# MarsLander.net
KiCad netlist of a schematic drawn in EAGLE
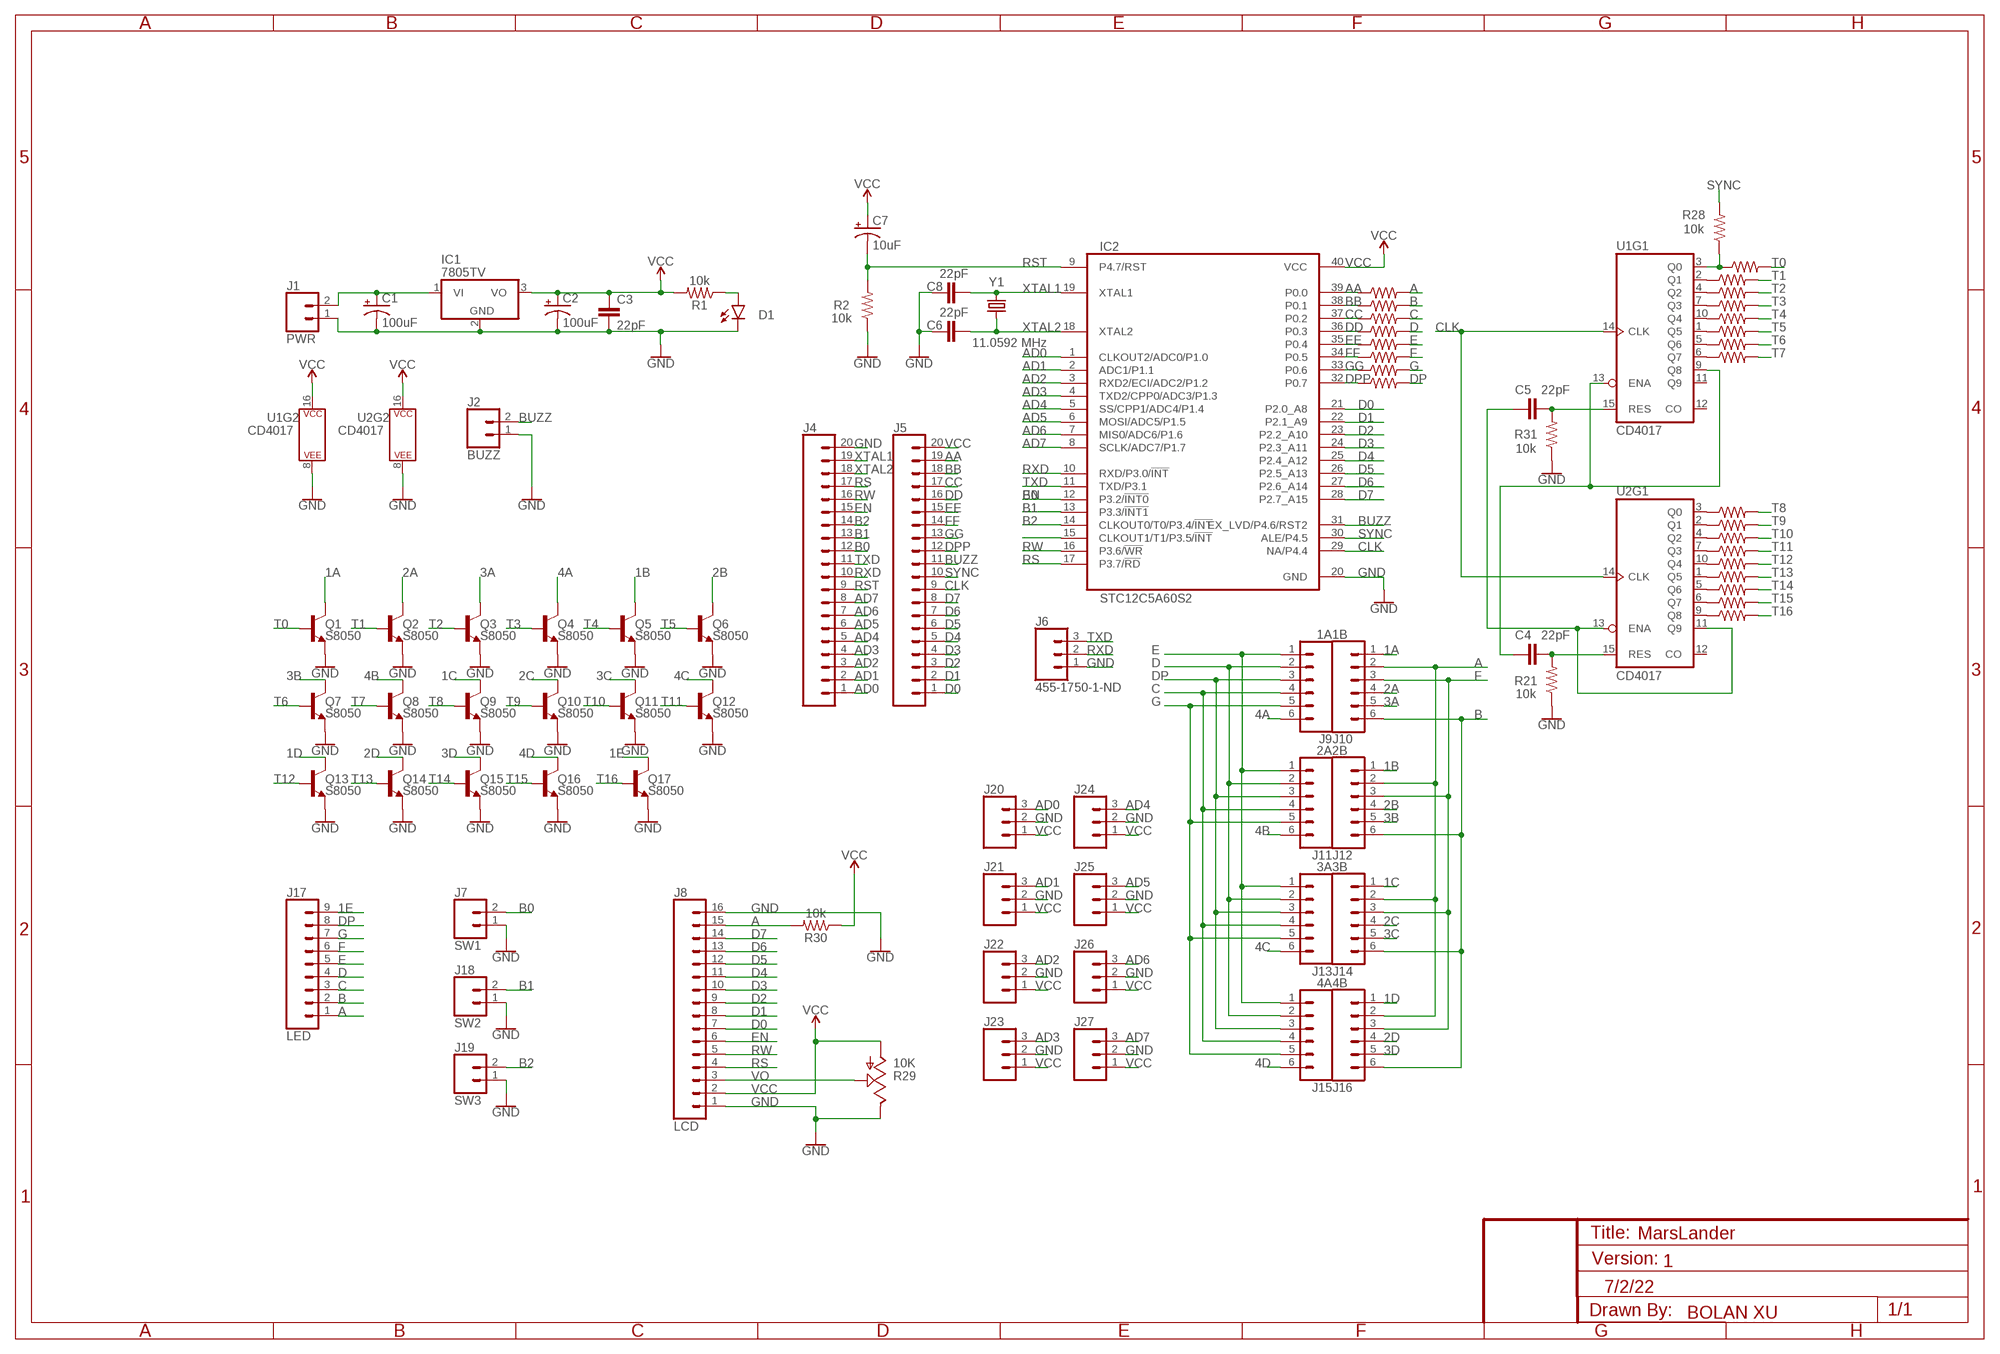
[diagram p0: schematic, sheet 1]

(export (version "E")
  (design (tool "Eeschema 10.0.6"))
  (components
    (comp (ref "C1")
      (value "100uF")
      (footprint "eagle-import:CPOL-RADIAL-2.5MM-6.5MM")
      (libsource (lib "eagle-import") (part "100UF-POLAR-RADIAL-2.5MM-25V-20%"))
    )
    (comp (ref "C2")
      (value "100uF")
      (footprint "eagle-import:CPOL-RADIAL-2.5MM-6.5MM")
      (libsource (lib "eagle-import") (part "100UF-POLAR-RADIAL-2.5MM-25V-20%"))
    )
    (comp (ref "C3")
      (value "22pF")
      (footprint "eagle-import:CAP-PTH-2.54")
      (libsource (lib "eagle-import") (part "22PF-PTH-2.54MM-200V-5%"))
    )
    (comp (ref "C4")
      (value "22pF")
      (footprint "eagle-import:CAP-PTH-2.54")
      (libsource (lib "eagle-import") (part "22PF-PTH-2.54MM-200V-5%"))
    )
    (comp (ref "C5")
      (value "22pF")
      (footprint "eagle-import:CAP-PTH-2.54")
      (libsource (lib "eagle-import") (part "22PF-PTH-2.54MM-200V-5%"))
    )
    (comp (ref "C6")
      (value "22pF")
      (footprint "eagle-import:CAP-PTH-2.54")
      (libsource (lib "eagle-import") (part "22PF-PTH-2.54MM-200V-5%"))
    )
    (comp (ref "C7")
      (value "10uF")
      (footprint "eagle-import:CPOL-RADIAL-2.5MM-5MM")
      (libsource (lib "eagle-import") (part "10UF-POLAR-RADIAL-2.5MM-25V-20%"))
    )
    (comp (ref "C8")
      (value "22pF")
      (footprint "eagle-import:CAP-PTH-2.54")
      (libsource (lib "eagle-import") (part "22PF-PTH-2.54MM-200V-5%"))
    )
    (comp (ref "D1")
      (value "3MM")
      (footprint "eagle-import:LED_3MM")
      (libsource (lib "eagle-import") (part "LED3MM"))
    )
    (comp (ref "IC1")
      (value "7805TV")
      (footprint "eagle-import:TO220V")
      (libsource (lib "eagle-import") (part "78TV05"))
    )
    (comp (ref "IC2")
      (value "STC12C5A60S2")
      (footprint "eagle-import:DIL40")
      (libsource (lib "eagle-import") (part "STC125A60S2P"))
    )
    (comp (ref "J1")
      (value "PWR")
      (footprint "eagle-import:1X02")
      (libsource (lib "eagle-import") (part "CONN_02"))
    )
    (comp (ref "J2")
      (value "BUZZ")
      (footprint "eagle-import:1X02")
      (libsource (lib "eagle-import") (part "CONN_02"))
    )
    (comp (ref "J4")
      (value "CONN_20")
      (footprint "eagle-import:1X20")
      (libsource (lib "eagle-import") (part "CONN_20"))
    )
    (comp (ref "J5")
      (value "CONN_20")
      (footprint "eagle-import:1X20")
      (libsource (lib "eagle-import") (part "CONN_20"))
    )
    (comp (ref "J6")
      (value "455-1750-1-ND")
      (footprint "eagle-import:1X03")
      (libsource (lib "eagle-import") (part "CONN_03"))
    )
    (comp (ref "J7")
      (value "SW1")
      (footprint "eagle-import:1X02")
      (libsource (lib "eagle-import") (part "CONN_02"))
    )
    (comp (ref "J8")
      (value "LCD")
      (footprint "eagle-import:1X16")
      (libsource (lib "eagle-import") (part "CONN_16"))
    )
    (comp (ref "J9")
      (value "1A")
      (footprint "eagle-import:1X06")
      (libsource (lib "eagle-import") (part "CONN_06SILK_FEMALE_PTH"))
    )
    (comp (ref "J10")
      (value "1B")
      (footprint "eagle-import:1X06")
      (libsource (lib "eagle-import") (part "CONN_06SILK_FEMALE_PTH"))
    )
    (comp (ref "J11")
      (value "2A")
      (footprint "eagle-import:1X06")
      (libsource (lib "eagle-import") (part "CONN_06SILK_FEMALE_PTH"))
    )
    (comp (ref "J12")
      (value "2B")
      (footprint "eagle-import:1X06")
      (libsource (lib "eagle-import") (part "CONN_06SILK_FEMALE_PTH"))
    )
    (comp (ref "J13")
      (value "3A")
      (footprint "eagle-import:1X06")
      (libsource (lib "eagle-import") (part "CONN_06SILK_FEMALE_PTH"))
    )
    (comp (ref "J14")
      (value "3B")
      (footprint "eagle-import:1X06")
      (libsource (lib "eagle-import") (part "CONN_06SILK_FEMALE_PTH"))
    )
    (comp (ref "J15")
      (value "4A")
      (footprint "eagle-import:1X06")
      (libsource (lib "eagle-import") (part "CONN_06SILK_FEMALE_PTH"))
    )
    (comp (ref "J16")
      (value "4B")
      (footprint "eagle-import:1X06")
      (libsource (lib "eagle-import") (part "CONN_06SILK_FEMALE_PTH"))
    )
    (comp (ref "J17")
      (value "LED")
      (footprint "eagle-import:1X09")
      (libsource (lib "eagle-import") (part "CONN_09"))
    )
    (comp (ref "J18")
      (value "SW2")
      (footprint "eagle-import:1X02")
      (libsource (lib "eagle-import") (part "CONN_02"))
    )
    (comp (ref "J19")
      (value "SW3")
      (footprint "eagle-import:1X02")
      (libsource (lib "eagle-import") (part "CONN_02"))
    )
    (comp (ref "J20")
      (value "455-1750-1-ND")
      (footprint "eagle-import:1X03")
      (libsource (lib "eagle-import") (part "CONN_03"))
    )
    (comp (ref "J21")
      (value "455-1750-1-ND")
      (footprint "eagle-import:1X03")
      (libsource (lib "eagle-import") (part "CONN_03"))
    )
    (comp (ref "J22")
      (value "455-1750-1-ND")
      (footprint "eagle-import:1X03")
      (libsource (lib "eagle-import") (part "CONN_03"))
    )
    (comp (ref "J23")
      (value "455-1750-1-ND")
      (footprint "eagle-import:1X03")
      (libsource (lib "eagle-import") (part "CONN_03"))
    )
    (comp (ref "J24")
      (value "455-1750-1-ND")
      (footprint "eagle-import:1X03")
      (libsource (lib "eagle-import") (part "CONN_03"))
    )
    (comp (ref "J25")
      (value "455-1750-1-ND")
      (footprint "eagle-import:1X03")
      (libsource (lib "eagle-import") (part "CONN_03"))
    )
    (comp (ref "J26")
      (value "455-1750-1-ND")
      (footprint "eagle-import:1X03")
      (libsource (lib "eagle-import") (part "CONN_03"))
    )
    (comp (ref "J27")
      (value "455-1750-1-ND")
      (footprint "eagle-import:1X03")
      (libsource (lib "eagle-import") (part "CONN_03"))
    )
    (comp (ref "Q1")
      (value "S8050")
      (footprint "eagle-import:TO-92")
      (libsource (lib "eagle-import") (part "TRANS_NPN-2N3904"))
    )
    (comp (ref "Q2")
      (value "S8050")
      (footprint "eagle-import:TO-92")
      (libsource (lib "eagle-import") (part "TRANS_NPN-2N3904"))
    )
    (comp (ref "Q3")
      (value "S8050")
      (footprint "eagle-import:TO-92")
      (libsource (lib "eagle-import") (part "TRANS_NPN-2N3904"))
    )
    (comp (ref "Q4")
      (value "S8050")
      (footprint "eagle-import:TO-92")
      (libsource (lib "eagle-import") (part "TRANS_NPN-2N3904"))
    )
    (comp (ref "Q5")
      (value "S8050")
      (footprint "eagle-import:TO-92")
      (libsource (lib "eagle-import") (part "TRANS_NPN-2N3904"))
    )
    (comp (ref "Q6")
      (value "S8050")
      (footprint "eagle-import:TO-92")
      (libsource (lib "eagle-import") (part "TRANS_NPN-2N3904"))
    )
    (comp (ref "Q7")
      (value "S8050")
      (footprint "eagle-import:TO-92")
      (libsource (lib "eagle-import") (part "TRANS_NPN-2N3904"))
    )
    (comp (ref "Q8")
      (value "S8050")
      (footprint "eagle-import:TO-92")
      (libsource (lib "eagle-import") (part "TRANS_NPN-2N3904"))
    )
    (comp (ref "Q9")
      (value "S8050")
      (footprint "eagle-import:TO-92")
      (libsource (lib "eagle-import") (part "TRANS_NPN-2N3904"))
    )
    (comp (ref "Q10")
      (value "S8050")
      (footprint "eagle-import:TO-92")
      (libsource (lib "eagle-import") (part "TRANS_NPN-2N3904"))
    )
    (comp (ref "Q11")
      (value "S8050")
      (footprint "eagle-import:TO-92")
      (libsource (lib "eagle-import") (part "TRANS_NPN-2N3904"))
    )
    (comp (ref "Q12")
      (value "S8050")
      (footprint "eagle-import:TO-92")
      (libsource (lib "eagle-import") (part "TRANS_NPN-2N3904"))
    )
    (comp (ref "Q13")
      (value "S8050")
      (footprint "eagle-import:TO-92")
      (libsource (lib "eagle-import") (part "TRANS_NPN-2N3904"))
    )
    (comp (ref "Q14")
      (value "S8050")
      (footprint "eagle-import:TO-92")
      (libsource (lib "eagle-import") (part "TRANS_NPN-2N3904"))
    )
    (comp (ref "Q15")
      (value "S8050")
      (footprint "eagle-import:TO-92")
      (libsource (lib "eagle-import") (part "TRANS_NPN-2N3904"))
    )
    (comp (ref "Q16")
      (value "S8050")
      (footprint "eagle-import:TO-92")
      (libsource (lib "eagle-import") (part "TRANS_NPN-2N3904"))
    )
    (comp (ref "Q17")
      (value "S8050")
      (footprint "eagle-import:TO-92")
      (libsource (lib "eagle-import") (part "TRANS_NPN-2N3904"))
    )
    (comp (ref "R1")
      (value "10k")
      (footprint "eagle-import:AXIAL-0.3")
      (libsource (lib "eagle-import") (part "10KOHM-HORIZ-1/4W-1%"))
    )
    (comp (ref "R2")
      (value "10k")
      (footprint "eagle-import:AXIAL-0.3")
      (libsource (lib "eagle-import") (part "10KOHM-HORIZ-1/4W-1%"))
    )
    (comp (ref "R3")
      (value "10k")
      (footprint "eagle-import:AXIAL-0.3")
      (libsource (lib "eagle-import") (part "10KOHM-HORIZ-1/4W-1%"))
    )
    (comp (ref "R4")
      (value "10k")
      (footprint "eagle-import:AXIAL-0.3")
      (libsource (lib "eagle-import") (part "10KOHM-HORIZ-1/4W-1%"))
    )
    (comp (ref "R5")
      (value "10k")
      (footprint "eagle-import:AXIAL-0.3")
      (libsource (lib "eagle-import") (part "10KOHM-HORIZ-1/4W-1%"))
    )
    (comp (ref "R6")
      (value "10k")
      (footprint "eagle-import:AXIAL-0.3")
      (libsource (lib "eagle-import") (part "10KOHM-HORIZ-1/4W-1%"))
    )
    (comp (ref "R7")
      (value "10k")
      (footprint "eagle-import:AXIAL-0.3")
      (libsource (lib "eagle-import") (part "10KOHM-HORIZ-1/4W-1%"))
    )
    (comp (ref "R8")
      (value "10k")
      (footprint "eagle-import:AXIAL-0.3")
      (libsource (lib "eagle-import") (part "10KOHM-HORIZ-1/4W-1%"))
    )
    (comp (ref "R9")
      (value "10k")
      (footprint "eagle-import:AXIAL-0.3")
      (libsource (lib "eagle-import") (part "10KOHM-HORIZ-1/4W-1%"))
    )
    (comp (ref "R10")
      (value "10k")
      (footprint "eagle-import:AXIAL-0.3")
      (libsource (lib "eagle-import") (part "10KOHM-HORIZ-1/4W-1%"))
    )
    (comp (ref "R11")
      (value "10k")
      (footprint "eagle-import:AXIAL-0.3")
      (libsource (lib "eagle-import") (part "10KOHM-HORIZ-1/4W-1%"))
    )
    (comp (ref "R12")
      (value "10k")
      (footprint "eagle-import:AXIAL-0.3")
      (libsource (lib "eagle-import") (part "10KOHM-HORIZ-1/4W-1%"))
    )
    (comp (ref "R13")
      (value "10k")
      (footprint "eagle-import:AXIAL-0.3")
      (libsource (lib "eagle-import") (part "10KOHM-HORIZ-1/4W-1%"))
    )
    (comp (ref "R14")
      (value "10k")
      (footprint "eagle-import:AXIAL-0.3")
      (libsource (lib "eagle-import") (part "10KOHM-HORIZ-1/4W-1%"))
    )
    (comp (ref "R15")
      (value "10k")
      (footprint "eagle-import:AXIAL-0.3")
      (libsource (lib "eagle-import") (part "10KOHM-HORIZ-1/4W-1%"))
    )
    (comp (ref "R16")
      (value "10k")
      (footprint "eagle-import:AXIAL-0.3")
      (libsource (lib "eagle-import") (part "10KOHM-HORIZ-1/4W-1%"))
    )
    (comp (ref "R17")
      (value "10k")
      (footprint "eagle-import:AXIAL-0.3")
      (libsource (lib "eagle-import") (part "10KOHM-HORIZ-1/4W-1%"))
    )
    (comp (ref "R18")
      (value "10k")
      (footprint "eagle-import:AXIAL-0.3")
      (libsource (lib "eagle-import") (part "10KOHM-HORIZ-1/4W-5%"))
    )
    (comp (ref "R19")
      (value "10k")
      (footprint "eagle-import:AXIAL-0.3")
      (libsource (lib "eagle-import") (part "10KOHM-HORIZ-1/4W-1%"))
    )
    (comp (ref "R20")
      (value "10k")
      (footprint "eagle-import:AXIAL-0.3")
      (libsource (lib "eagle-import") (part "10KOHM-HORIZ-1/4W-1%"))
    )
    (comp (ref "R21")
      (value "10k")
      (footprint "eagle-import:AXIAL-0.3")
      (libsource (lib "eagle-import") (part "10KOHM-HORIZ-1/4W-1%"))
    )
    (comp (ref "R22")
      (value "10k")
      (footprint "eagle-import:AXIAL-0.3")
      (libsource (lib "eagle-import") (part "10KOHM-HORIZ-1/4W-1%"))
    )
    (comp (ref "R23")
      (value "10k")
      (footprint "eagle-import:AXIAL-0.3")
      (libsource (lib "eagle-import") (part "10KOHM-HORIZ-1/4W-1%"))
    )
    (comp (ref "R24")
      (value "10k")
      (footprint "eagle-import:AXIAL-0.3")
      (libsource (lib "eagle-import") (part "10KOHM-HORIZ-1/4W-1%"))
    )
    (comp (ref "R25")
      (value "10k")
      (footprint "eagle-import:AXIAL-0.3")
      (libsource (lib "eagle-import") (part "10KOHM-HORIZ-1/4W-1%"))
    )
    (comp (ref "R26")
      (value "10k")
      (footprint "eagle-import:AXIAL-0.3")
      (libsource (lib "eagle-import") (part "10KOHM-HORIZ-1/4W-1%"))
    )
    (comp (ref "R27")
      (value "10k")
      (footprint "eagle-import:AXIAL-0.3")
      (libsource (lib "eagle-import") (part "10KOHM-HORIZ-1/4W-1%"))
    )
    (comp (ref "R28")
      (value "10k")
      (footprint "eagle-import:AXIAL-0.3")
      (libsource (lib "eagle-import") (part "10KOHM-HORIZ-1/4W-1%"))
    )
    (comp (ref "R29")
      (value "10K")
      (footprint "eagle-import:B25P")
      (libsource (lib "eagle-import") (part "TRIM_US-B25P"))
    )
    (comp (ref "R30")
      (value "10k")
      (footprint "eagle-import:AXIAL-0.3")
      (libsource (lib "eagle-import") (part "10KOHM-HORIZ-1/4W-1%"))
    )
    (comp (ref "R31")
      (value "10k")
      (footprint "eagle-import:AXIAL-0.3")
      (libsource (lib "eagle-import") (part "10KOHM-HORIZ-1/4W-1%"))
    )
    (comp (ref "R33")
      (value "10k")
      (footprint "eagle-import:AXIAL-0.3")
      (libsource (lib "eagle-import") (part "10KOHM-HORIZ-1/4W-1%"))
    )
    (comp (ref "U1")
      (value "CD4017")
      (footprint "eagle-import:DIP16")
      (libsource (lib "eagle-import") (part "CD4017"))
    )
    (comp (ref "U2")
      (value "CD4017")
      (footprint "eagle-import:DIP16")
      (libsource (lib "eagle-import") (part "CD4017"))
    )
    (comp (ref "Y1")
      (value "11.0592 MHz")
      (footprint "eagle-import:HC49U")
      (libsource (lib "eagle-import") (part "CRYSTALPTH-HC49UV"))
    )
  )
  (nets
    (net (code "1") (name "/1A") (class "Default")
      (node (ref "J10") (pin "1") (pinfunction "1_1") (pintype "passive"))
      (node (ref "Q1") (pin "3") (pinfunction "C_3") (pintype "passive"))
    )
    (net (code "2") (name "/1B") (class "Default")
      (node (ref "J12") (pin "1") (pinfunction "1_1") (pintype "passive"))
      (node (ref "Q5") (pin "3") (pinfunction "C_3") (pintype "passive"))
    )
    (net (code "3") (name "/1C") (class "Default")
      (node (ref "J14") (pin "1") (pinfunction "1_1") (pintype "passive"))
      (node (ref "Q9") (pin "3") (pinfunction "C_3") (pintype "passive"))
    )
    (net (code "4") (name "/1D") (class "Default")
      (node (ref "J16") (pin "1") (pinfunction "1_1") (pintype "passive"))
      (node (ref "Q13") (pin "3") (pinfunction "C_3") (pintype "passive"))
    )
    (net (code "5") (name "/1E") (class "Default")
      (node (ref "J17") (pin "9") (pinfunction "9_9") (pintype "passive"))
      (node (ref "Q17") (pin "3") (pinfunction "C_3") (pintype "passive"))
    )
    (net (code "6") (name "/2A") (class "Default")
      (node (ref "J10") (pin "4") (pinfunction "4_4") (pintype "passive"))
      (node (ref "Q2") (pin "3") (pinfunction "C_3") (pintype "passive"))
    )
    (net (code "7") (name "/2B") (class "Default")
      (node (ref "J12") (pin "4") (pinfunction "4_4") (pintype "passive"))
      (node (ref "Q6") (pin "3") (pinfunction "C_3") (pintype "passive"))
    )
    (net (code "8") (name "/2C") (class "Default")
      (node (ref "J14") (pin "4") (pinfunction "4_4") (pintype "passive"))
      (node (ref "Q10") (pin "3") (pinfunction "C_3") (pintype "passive"))
    )
    (net (code "9") (name "/2D") (class "Default")
      (node (ref "J16") (pin "4") (pinfunction "4_4") (pintype "passive"))
      (node (ref "Q14") (pin "3") (pinfunction "C_3") (pintype "passive"))
    )
    (net (code "10") (name "/3A") (class "Default")
      (node (ref "J10") (pin "5") (pinfunction "5_5") (pintype "passive"))
      (node (ref "Q3") (pin "3") (pinfunction "C_3") (pintype "passive"))
    )
    (net (code "11") (name "/3B") (class "Default")
      (node (ref "J12") (pin "5") (pinfunction "5_5") (pintype "passive"))
      (node (ref "Q7") (pin "3") (pinfunction "C_3") (pintype "passive"))
    )
    (net (code "12") (name "/3C") (class "Default")
      (node (ref "J14") (pin "5") (pinfunction "5_5") (pintype "passive"))
      (node (ref "Q11") (pin "3") (pinfunction "C_3") (pintype "passive"))
    )
    (net (code "13") (name "/3D") (class "Default")
      (node (ref "J16") (pin "5") (pinfunction "5_5") (pintype "passive"))
      (node (ref "Q15") (pin "3") (pinfunction "C_3") (pintype "passive"))
    )
    (net (code "14") (name "/4A") (class "Default")
      (node (ref "J9") (pin "6") (pinfunction "6_6") (pintype "passive"))
      (node (ref "Q4") (pin "3") (pinfunction "C_3") (pintype "passive"))
    )
    (net (code "15") (name "/4B") (class "Default")
      (node (ref "J11") (pin "6") (pinfunction "6_6") (pintype "passive"))
      (node (ref "Q8") (pin "3") (pinfunction "C_3") (pintype "passive"))
    )
    (net (code "16") (name "/4C") (class "Default")
      (node (ref "J13") (pin "6") (pinfunction "6_6") (pintype "passive"))
      (node (ref "Q12") (pin "3") (pinfunction "C_3") (pintype "passive"))
    )
    (net (code "17") (name "/4D") (class "Default")
      (node (ref "J15") (pin "6") (pinfunction "6_6") (pintype "passive"))
      (node (ref "Q16") (pin "3") (pinfunction "C_3") (pintype "passive"))
    )
    (net (code "18") (name "/A") (class "Default")
      (node (ref "J10") (pin "2") (pinfunction "2_2") (pintype "passive"))
      (node (ref "J12") (pin "2") (pinfunction "2_2") (pintype "passive"))
      (node (ref "J14") (pin "2") (pinfunction "2_2") (pintype "passive"))
      (node (ref "J16") (pin "2") (pinfunction "2_2") (pintype "passive"))
      (node (ref "J17") (pin "1") (pinfunction "1_1") (pintype "passive"))
      (node (ref "J8") (pin "15") (pinfunction "15_15") (pintype "passive"))
      (node (ref "R19") (pin "P$2") (pinfunction "2_P$2") (pintype "passive"))
      (node (ref "R30") (pin "P$2") (pinfunction "2_P$2") (pintype "passive"))
    )
    (net (code "19") (name "/AA") (class "Default")
      (node (ref "IC2") (pin "39") (pinfunction "P0.0_39") (pintype "bidirectional"))
      (node (ref "J5") (pin "19") (pinfunction "19_19") (pintype "passive"))
      (node (ref "R19") (pin "P$1") (pinfunction "1_P$1") (pintype "passive"))
    )
    (net (code "20") (name "/AD0") (class "Default")
      (node (ref "IC2") (pin "1") (pinfunction "CLKOUT2/ADC0/P1.0_1") (pintype "bidirectional"))
      (node (ref "J20") (pin "3") (pinfunction "3_3") (pintype "passive"))
      (node (ref "J4") (pin "1") (pinfunction "1_1") (pintype "passive"))
    )
    (net (code "21") (name "/AD1") (class "Default")
      (node (ref "IC2") (pin "2") (pinfunction "ADC1/P1.1_2") (pintype "bidirectional"))
      (node (ref "J21") (pin "3") (pinfunction "3_3") (pintype "passive"))
      (node (ref "J4") (pin "2") (pinfunction "2_2") (pintype "passive"))
    )
    (net (code "22") (name "/AD2") (class "Default")
      (node (ref "IC2") (pin "3") (pinfunction "RXD2/ECI/ADC2/P1.2_3") (pintype "bidirectional"))
      (node (ref "J22") (pin "3") (pinfunction "3_3") (pintype "passive"))
      (node (ref "J4") (pin "3") (pinfunction "3_3") (pintype "passive"))
    )
    (net (code "23") (name "/AD3") (class "Default")
      (node (ref "IC2") (pin "4") (pinfunction "TXD2/CPP0/ADC3/P1.3_4") (pintype "bidirectional"))
      (node (ref "J23") (pin "3") (pinfunction "3_3") (pintype "passive"))
      (node (ref "J4") (pin "4") (pinfunction "4_4") (pintype "passive"))
    )
    (net (code "24") (name "/AD4") (class "Default")
      (node (ref "IC2") (pin "5") (pinfunction "SS/CPP1/ADC4/P1.4_5") (pintype "bidirectional"))
      (node (ref "J24") (pin "3") (pinfunction "3_3") (pintype "passive"))
      (node (ref "J4") (pin "5") (pinfunction "5_5") (pintype "passive"))
    )
    (net (code "25") (name "/AD5") (class "Default")
      (node (ref "IC2") (pin "6") (pinfunction "MOSI/ADC5/P1.5_6") (pintype "bidirectional"))
      (node (ref "J25") (pin "3") (pinfunction "3_3") (pintype "passive"))
      (node (ref "J4") (pin "6") (pinfunction "6_6") (pintype "passive"))
    )
    (net (code "26") (name "/AD6") (class "Default")
      (node (ref "IC2") (pin "7") (pinfunction "MIS0/ADC6/P1.6_7") (pintype "bidirectional"))
      (node (ref "J26") (pin "3") (pinfunction "3_3") (pintype "passive"))
      (node (ref "J4") (pin "7") (pinfunction "7_7") (pintype "passive"))
    )
    (net (code "27") (name "/AD7") (class "Default")
      (node (ref "IC2") (pin "8") (pinfunction "SCLK/ADC7/P1.7_8") (pintype "bidirectional"))
      (node (ref "J27") (pin "3") (pinfunction "3_3") (pintype "passive"))
      (node (ref "J4") (pin "8") (pinfunction "8_8") (pintype "passive"))
    )
    (net (code "28") (name "/B") (class "Default")
      (node (ref "J10") (pin "6") (pinfunction "6_6") (pintype "passive"))
      (node (ref "J12") (pin "6") (pinfunction "6_6") (pintype "passive"))
      (node (ref "J14") (pin "6") (pinfunction "6_6") (pintype "passive"))
      (node (ref "J16") (pin "6") (pinfunction "6_6") (pintype "passive"))
      (node (ref "J17") (pin "2") (pinfunction "2_2") (pintype "passive"))
      (node (ref "R20") (pin "P$2") (pinfunction "2_P$2") (pintype "passive"))
    )
    (net (code "29") (name "/B0") (class "Default")
      (node (ref "IC2") (pin "12") (pinfunction "P3.2/~{INT0}_12") (pintype "bidirectional"))
      (node (ref "J4") (pin "12") (pinfunction "12_12") (pintype "passive"))
      (node (ref "J7") (pin "2") (pinfunction "2_2") (pintype "passive"))
    )
    (net (code "30") (name "/B1") (class "Default")
      (node (ref "IC2") (pin "13") (pinfunction "P3.3/~{INT1}_13") (pintype "bidirectional"))
      (node (ref "J18") (pin "2") (pinfunction "2_2") (pintype "passive"))
      (node (ref "J4") (pin "13") (pinfunction "13_13") (pintype "passive"))
    )
    (net (code "31") (name "/B2") (class "Default")
      (node (ref "IC2") (pin "14") (pinfunction "CLKOUT0/T0/P3.4/~{INT}_14") (pintype "bidirectional"))
      (node (ref "J19") (pin "2") (pinfunction "2_2") (pintype "passive"))
      (node (ref "J4") (pin "14") (pinfunction "14_14") (pintype "passive"))
    )
    (net (code "32") (name "/BB") (class "Default")
      (node (ref "IC2") (pin "38") (pinfunction "P0.1_38") (pintype "bidirectional"))
      (node (ref "J5") (pin "18") (pinfunction "18_18") (pintype "passive"))
      (node (ref "R20") (pin "P$1") (pinfunction "1_P$1") (pintype "passive"))
    )
    (net (code "33") (name "/BUZZ") (class "Default")
      (node (ref "IC2") (pin "31") (pinfunction "EX_LVD/P4.6/RST2_31") (pintype "input"))
      (node (ref "J2") (pin "2") (pinfunction "2_2") (pintype "passive"))
      (node (ref "J5") (pin "11") (pinfunction "11_11") (pintype "passive"))
    )
    (net (code "34") (name "/C") (class "Default")
      (node (ref "J11") (pin "4") (pinfunction "4_4") (pintype "passive"))
      (node (ref "J13") (pin "4") (pinfunction "4_4") (pintype "passive"))
      (node (ref "J15") (pin "4") (pinfunction "4_4") (pintype "passive"))
      (node (ref "J17") (pin "3") (pinfunction "3_3") (pintype "passive"))
      (node (ref "J9") (pin "4") (pinfunction "4_4") (pintype "passive"))
      (node (ref "R22") (pin "P$2") (pinfunction "2_P$2") (pintype "passive"))
    )
    (net (code "35") (name "/CC") (class "Default")
      (node (ref "IC2") (pin "37") (pinfunction "P0.2_37") (pintype "bidirectional"))
      (node (ref "J5") (pin "17") (pinfunction "17_17") (pintype "passive"))
      (node (ref "R22") (pin "P$1") (pinfunction "1_P$1") (pintype "passive"))
    )
    (net (code "36") (name "/CLK") (class "Default")
      (node (ref "IC2") (pin "29") (pinfunction "NA/P4.4_29") (pintype "output"))
      (node (ref "J5") (pin "9") (pinfunction "9_9") (pintype "passive"))
      (node (ref "U1") (pin "14") (pinfunction "CLK_14") (pintype "input"))
      (node (ref "U2") (pin "14") (pinfunction "CLK_14") (pintype "input"))
    )
    (net (code "37") (name "/D") (class "Default")
      (node (ref "J11") (pin "2") (pinfunction "2_2") (pintype "passive"))
      (node (ref "J13") (pin "2") (pinfunction "2_2") (pintype "passive"))
      (node (ref "J15") (pin "2") (pinfunction "2_2") (pintype "passive"))
      (node (ref "J17") (pin "4") (pinfunction "4_4") (pintype "passive"))
      (node (ref "J9") (pin "2") (pinfunction "2_2") (pintype "passive"))
      (node (ref "R23") (pin "P$2") (pinfunction "2_P$2") (pintype "passive"))
    )
    (net (code "38") (name "/D0") (class "Default")
      (node (ref "IC2") (pin "21") (pinfunction "P2.0_A8_21") (pintype "bidirectional"))
      (node (ref "J5") (pin "1") (pinfunction "1_1") (pintype "passive"))
      (node (ref "J8") (pin "7") (pinfunction "7_7") (pintype "passive"))
    )
    (net (code "39") (name "/D1") (class "Default")
      (node (ref "IC2") (pin "22") (pinfunction "P2.1_A9_22") (pintype "bidirectional"))
      (node (ref "J5") (pin "2") (pinfunction "2_2") (pintype "passive"))
      (node (ref "J8") (pin "8") (pinfunction "8_8") (pintype "passive"))
    )
    (net (code "40") (name "/D2") (class "Default")
      (node (ref "IC2") (pin "23") (pinfunction "P2.2_A10_23") (pintype "bidirectional"))
      (node (ref "J5") (pin "3") (pinfunction "3_3") (pintype "passive"))
      (node (ref "J8") (pin "9") (pinfunction "9_9") (pintype "passive"))
    )
    (net (code "41") (name "/D3") (class "Default")
      (node (ref "IC2") (pin "24") (pinfunction "P2.3_A11_24") (pintype "bidirectional"))
      (node (ref "J5") (pin "4") (pinfunction "4_4") (pintype "passive"))
      (node (ref "J8") (pin "10") (pinfunction "10_10") (pintype "passive"))
    )
    (net (code "42") (name "/D4") (class "Default")
      (node (ref "IC2") (pin "25") (pinfunction "P2.4_A12_25") (pintype "bidirectional"))
      (node (ref "J5") (pin "5") (pinfunction "5_5") (pintype "passive"))
      (node (ref "J8") (pin "11") (pinfunction "11_11") (pintype "passive"))
    )
    (net (code "43") (name "/D5") (class "Default")
      (node (ref "IC2") (pin "26") (pinfunction "P2.5_A13_26") (pintype "bidirectional"))
      (node (ref "J5") (pin "6") (pinfunction "6_6") (pintype "passive"))
      (node (ref "J8") (pin "12") (pinfunction "12_12") (pintype "passive"))
    )
    (net (code "44") (name "/D6") (class "Default")
      (node (ref "IC2") (pin "27") (pinfunction "P2.6_A14_27") (pintype "bidirectional"))
      (node (ref "J5") (pin "7") (pinfunction "7_7") (pintype "passive"))
      (node (ref "J8") (pin "13") (pinfunction "13_13") (pintype "passive"))
    )
    (net (code "45") (name "/D7") (class "Default")
      (node (ref "IC2") (pin "28") (pinfunction "P2.7_A15_28") (pintype "bidirectional"))
      (node (ref "J5") (pin "8") (pinfunction "8_8") (pintype "passive"))
      (node (ref "J8") (pin "14") (pinfunction "14_14") (pintype "passive"))
    )
    (net (code "46") (name "/DD") (class "Default")
      (node (ref "IC2") (pin "36") (pinfunction "P0.3_36") (pintype "bidirectional"))
      (node (ref "J5") (pin "16") (pinfunction "16_16") (pintype "passive"))
      (node (ref "R23") (pin "P$1") (pinfunction "1_P$1") (pintype "passive"))
    )
    (net (code "47") (name "/DP") (class "Default")
      (node (ref "J11") (pin "3") (pinfunction "3_3") (pintype "passive"))
      (node (ref "J13") (pin "3") (pinfunction "3_3") (pintype "passive"))
      (node (ref "J15") (pin "3") (pinfunction "3_3") (pintype "passive"))
      (node (ref "J17") (pin "8") (pinfunction "8_8") (pintype "passive"))
      (node (ref "J9") (pin "3") (pinfunction "3_3") (pintype "passive"))
      (node (ref "R27") (pin "P$2") (pinfunction "2_P$2") (pintype "passive"))
    )
    (net (code "48") (name "/DPP") (class "Default")
      (node (ref "IC2") (pin "32") (pinfunction "P0.7_32") (pintype "bidirectional"))
      (node (ref "J5") (pin "12") (pinfunction "12_12") (pintype "passive"))
      (node (ref "R27") (pin "P$1") (pinfunction "1_P$1") (pintype "passive"))
    )
    (net (code "49") (name "/E") (class "Default")
      (node (ref "J11") (pin "1") (pinfunction "1_1") (pintype "passive"))
      (node (ref "J13") (pin "1") (pinfunction "1_1") (pintype "passive"))
      (node (ref "J15") (pin "1") (pinfunction "1_1") (pintype "passive"))
      (node (ref "J17") (pin "5") (pinfunction "5_5") (pintype "passive"))
      (node (ref "J9") (pin "1") (pinfunction "1_1") (pintype "passive"))
      (node (ref "R24") (pin "P$2") (pinfunction "2_P$2") (pintype "passive"))
    )
    (net (code "50") (name "/EE") (class "Default")
      (node (ref "IC2") (pin "35") (pinfunction "P0.4_35") (pintype "bidirectional"))
      (node (ref "J5") (pin "15") (pinfunction "15_15") (pintype "passive"))
      (node (ref "R24") (pin "P$1") (pinfunction "1_P$1") (pintype "passive"))
    )
    (net (code "51") (name "/EN") (class "Default")
      (node (ref "IC2") (pin "15") (pinfunction "CLKOUT1/T1/P3.5/~{INT}_15") (pintype "bidirectional"))
      (node (ref "J4") (pin "15") (pinfunction "15_15") (pintype "passive"))
      (node (ref "J8") (pin "6") (pinfunction "6_6") (pintype "passive"))
    )
    (net (code "52") (name "/F") (class "Default")
      (node (ref "J10") (pin "3") (pinfunction "3_3") (pintype "passive"))
      (node (ref "J12") (pin "3") (pinfunction "3_3") (pintype "passive"))
      (node (ref "J14") (pin "3") (pinfunction "3_3") (pintype "passive"))
      (node (ref "J16") (pin "3") (pinfunction "3_3") (pintype "passive"))
      (node (ref "J17") (pin "6") (pinfunction "6_6") (pintype "passive"))
      (node (ref "R25") (pin "P$2") (pinfunction "2_P$2") (pintype "passive"))
    )
    (net (code "53") (name "/FF") (class "Default")
      (node (ref "IC2") (pin "34") (pinfunction "P0.5_34") (pintype "bidirectional"))
      (node (ref "J5") (pin "14") (pinfunction "14_14") (pintype "passive"))
      (node (ref "R25") (pin "P$1") (pinfunction "1_P$1") (pintype "passive"))
    )
    (net (code "54") (name "/G") (class "Default")
      (node (ref "J11") (pin "5") (pinfunction "5_5") (pintype "passive"))
      (node (ref "J13") (pin "5") (pinfunction "5_5") (pintype "passive"))
      (node (ref "J15") (pin "5") (pinfunction "5_5") (pintype "passive"))
      (node (ref "J17") (pin "7") (pinfunction "7_7") (pintype "passive"))
      (node (ref "J9") (pin "5") (pinfunction "5_5") (pintype "passive"))
      (node (ref "R26") (pin "P$2") (pinfunction "2_P$2") (pintype "passive"))
    )
    (net (code "55") (name "/GG") (class "Default")
      (node (ref "IC2") (pin "33") (pinfunction "P0.6_33") (pintype "bidirectional"))
      (node (ref "J5") (pin "13") (pinfunction "13_13") (pintype "passive"))
      (node (ref "R26") (pin "P$1") (pinfunction "1_P$1") (pintype "passive"))
    )
    (net (code "56") (name "/RS") (class "Default")
      (node (ref "IC2") (pin "17") (pinfunction "P3.7/~{RD}_17") (pintype "bidirectional"))
      (node (ref "J4") (pin "17") (pinfunction "17_17") (pintype "passive"))
      (node (ref "J8") (pin "4") (pinfunction "4_4") (pintype "passive"))
    )
    (net (code "57") (name "/RST") (class "Default")
      (node (ref "C7") (pin "2") (pinfunction "-_2") (pintype "passive"))
      (node (ref "IC2") (pin "9") (pinfunction "P4.7/RST_9") (pintype "bidirectional"))
      (node (ref "J4") (pin "9") (pinfunction "9_9") (pintype "passive"))
      (node (ref "R2") (pin "P$2") (pinfunction "2_P$2") (pintype "passive"))
    )
    (net (code "58") (name "/RW") (class "Default")
      (node (ref "IC2") (pin "16") (pinfunction "P3.6/~{WR}_16") (pintype "bidirectional"))
      (node (ref "J4") (pin "16") (pinfunction "16_16") (pintype "passive"))
      (node (ref "J8") (pin "5") (pinfunction "5_5") (pintype "passive"))
    )
    (net (code "59") (name "/RXD") (class "Default")
      (node (ref "IC2") (pin "10") (pinfunction "RXD/P3.0/~{INT}_10") (pintype "bidirectional"))
      (node (ref "J4") (pin "10") (pinfunction "10_10") (pintype "passive"))
      (node (ref "J6") (pin "2") (pinfunction "2_2") (pintype "passive"))
    )
    (net (code "60") (name "/SYNC") (class "Default")
      (node (ref "IC2") (pin "30") (pinfunction "ALE/P4.5_30") (pintype "output"))
      (node (ref "J5") (pin "10") (pinfunction "10_10") (pintype "passive"))
      (node (ref "R28") (pin "P$2") (pinfunction "2_P$2") (pintype "passive"))
    )
    (net (code "61") (name "/T0") (class "Default")
      (node (ref "Q1") (pin "2") (pinfunction "B_2") (pintype "passive"))
      (node (ref "R33") (pin "P$2") (pinfunction "2_P$2") (pintype "passive"))
    )
    (net (code "62") (name "/T1") (class "Default")
      (node (ref "Q2") (pin "2") (pinfunction "B_2") (pintype "passive"))
      (node (ref "R3") (pin "P$2") (pinfunction "2_P$2") (pintype "passive"))
    )
    (net (code "63") (name "/T2") (class "Default")
      (node (ref "Q3") (pin "2") (pinfunction "B_2") (pintype "passive"))
      (node (ref "R4") (pin "P$2") (pinfunction "2_P$2") (pintype "passive"))
    )
    (net (code "64") (name "/T3") (class "Default")
      (node (ref "Q4") (pin "2") (pinfunction "B_2") (pintype "passive"))
      (node (ref "R5") (pin "P$2") (pinfunction "2_P$2") (pintype "passive"))
    )
    (net (code "65") (name "/T4") (class "Default")
      (node (ref "Q5") (pin "2") (pinfunction "B_2") (pintype "passive"))
      (node (ref "R6") (pin "P$2") (pinfunction "2_P$2") (pintype "passive"))
    )
    (net (code "66") (name "/T5") (class "Default")
      (node (ref "Q6") (pin "2") (pinfunction "B_2") (pintype "passive"))
      (node (ref "R7") (pin "P$2") (pinfunction "2_P$2") (pintype "passive"))
    )
    (net (code "67") (name "/T6") (class "Default")
      (node (ref "Q7") (pin "2") (pinfunction "B_2") (pintype "passive"))
      (node (ref "R8") (pin "P$2") (pinfunction "2_P$2") (pintype "passive"))
    )
    (net (code "68") (name "/T7") (class "Default")
      (node (ref "Q8") (pin "2") (pinfunction "B_2") (pintype "passive"))
      (node (ref "R9") (pin "P$2") (pinfunction "2_P$2") (pintype "passive"))
    )
    (net (code "69") (name "/T8") (class "Default")
      (node (ref "Q9") (pin "2") (pinfunction "B_2") (pintype "passive"))
      (node (ref "R10") (pin "P$2") (pinfunction "2_P$2") (pintype "passive"))
    )
    (net (code "70") (name "/T9") (class "Default")
      (node (ref "Q10") (pin "2") (pinfunction "B_2") (pintype "passive"))
      (node (ref "R11") (pin "P$2") (pinfunction "2_P$2") (pintype "passive"))
    )
    (net (code "71") (name "/T10") (class "Default")
      (node (ref "Q11") (pin "2") (pinfunction "B_2") (pintype "passive"))
      (node (ref "R12") (pin "P$2") (pinfunction "2_P$2") (pintype "passive"))
    )
    (net (code "72") (name "/T11") (class "Default")
      (node (ref "Q12") (pin "2") (pinfunction "B_2") (pintype "passive"))
      (node (ref "R13") (pin "P$2") (pinfunction "2_P$2") (pintype "passive"))
    )
    (net (code "73") (name "/T12") (class "Default")
      (node (ref "Q13") (pin "2") (pinfunction "B_2") (pintype "passive"))
      (node (ref "R14") (pin "P$2") (pinfunction "2_P$2") (pintype "passive"))
    )
    (net (code "74") (name "/T13") (class "Default")
      (node (ref "Q14") (pin "2") (pinfunction "B_2") (pintype "passive"))
      (node (ref "R15") (pin "P$2") (pinfunction "2_P$2") (pintype "passive"))
    )
    (net (code "75") (name "/T14") (class "Default")
      (node (ref "Q15") (pin "2") (pinfunction "B_2") (pintype "passive"))
      (node (ref "R16") (pin "P$2") (pinfunction "2_P$2") (pintype "passive"))
    )
    (net (code "76") (name "/T15") (class "Default")
      (node (ref "Q16") (pin "2") (pinfunction "B_2") (pintype "passive"))
      (node (ref "R17") (pin "P$2") (pinfunction "2_P$2") (pintype "passive"))
    )
    (net (code "77") (name "/T16") (class "Default")
      (node (ref "Q17") (pin "2") (pinfunction "B_2") (pintype "passive"))
      (node (ref "R18") (pin "P$2") (pinfunction "2_P$2") (pintype "passive"))
    )
    (net (code "78") (name "/TXD") (class "Default")
      (node (ref "IC2") (pin "11") (pinfunction "TXD/P3.1_11") (pintype "bidirectional"))
      (node (ref "J4") (pin "11") (pinfunction "11_11") (pintype "passive"))
      (node (ref "J6") (pin "3") (pinfunction "3_3") (pintype "passive"))
    )
    (net (code "79") (name "/VO") (class "Default")
      (node (ref "J8") (pin "3") (pinfunction "3_3") (pintype "passive"))
      (node (ref "R29") (pin "S") (pinfunction "S_S") (pintype "passive"))
    )
    (net (code "80") (name "/XTAL1") (class "Default")
      (node (ref "C8") (pin "2") (pinfunction "2_2") (pintype "passive"))
      (node (ref "IC2") (pin "19") (pinfunction "XTAL1_19") (pintype "input"))
      (node (ref "J4") (pin "19") (pinfunction "19_19") (pintype "passive"))
      (node (ref "Y1") (pin "2") (pinfunction "2_2") (pintype "passive"))
    )
    (net (code "81") (name "/XTAL2") (class "Default")
      (node (ref "C6") (pin "2") (pinfunction "2_2") (pintype "passive"))
      (node (ref "IC2") (pin "18") (pinfunction "XTAL2_18") (pintype "input"))
      (node (ref "J4") (pin "18") (pinfunction "18_18") (pintype "passive"))
      (node (ref "Y1") (pin "1") (pinfunction "1_1") (pintype "passive"))
    )
    (net (code "82") (name "GND") (class "Default")
      (node (ref "C1") (pin "2") (pinfunction "-_2") (pintype "passive"))
      (node (ref "C2") (pin "2") (pinfunction "-_2") (pintype "passive"))
      (node (ref "C3") (pin "2") (pinfunction "2_2") (pintype "passive"))
      (node (ref "C6") (pin "1") (pinfunction "1_1") (pintype "passive"))
      (node (ref "C8") (pin "1") (pinfunction "1_1") (pintype "passive"))
      (node (ref "D1") (pin "K") (pinfunction "C_K") (pintype "passive"))
      (node (ref "IC1") (pin "2") (pinfunction "GND_2") (pintype "passive"))
      (node (ref "IC2") (pin "20") (pinfunction "GND_20") (pintype "power_in"))
      (node (ref "J1") (pin "1") (pinfunction "1_1") (pintype "passive"))
      (node (ref "J18") (pin "1") (pinfunction "1_1") (pintype "passive"))
      (node (ref "J19") (pin "1") (pinfunction "1_1") (pintype "passive"))
      (node (ref "J2") (pin "1") (pinfunction "1_1") (pintype "passive"))
      (node (ref "J20") (pin "2") (pinfunction "2_2") (pintype "passive"))
      (node (ref "J21") (pin "2") (pinfunction "2_2") (pintype "passive"))
      (node (ref "J22") (pin "2") (pinfunction "2_2") (pintype "passive"))
      (node (ref "J23") (pin "2") (pinfunction "2_2") (pintype "passive"))
      (node (ref "J24") (pin "2") (pinfunction "2_2") (pintype "passive"))
      (node (ref "J25") (pin "2") (pinfunction "2_2") (pintype "passive"))
      (node (ref "J26") (pin "2") (pinfunction "2_2") (pintype "passive"))
      (node (ref "J27") (pin "2") (pinfunction "2_2") (pintype "passive"))
      (node (ref "J4") (pin "20") (pinfunction "20_20") (pintype "passive"))
      (node (ref "J6") (pin "1") (pinfunction "1_1") (pintype "passive"))
      (node (ref "J7") (pin "1") (pinfunction "1_1") (pintype "passive"))
      (node (ref "J8") (pin "1") (pinfunction "1_1") (pintype "passive"))
      (node (ref "J8") (pin "16") (pinfunction "16_16") (pintype "passive"))
      (node (ref "Q1") (pin "1") (pinfunction "E_1") (pintype "passive"))
      (node (ref "Q10") (pin "1") (pinfunction "E_1") (pintype "passive"))
      (node (ref "Q11") (pin "1") (pinfunction "E_1") (pintype "passive"))
      (node (ref "Q12") (pin "1") (pinfunction "E_1") (pintype "passive"))
      (node (ref "Q13") (pin "1") (pinfunction "E_1") (pintype "passive"))
      (node (ref "Q14") (pin "1") (pinfunction "E_1") (pintype "passive"))
      (node (ref "Q15") (pin "1") (pinfunction "E_1") (pintype "passive"))
      (node (ref "Q16") (pin "1") (pinfunction "E_1") (pintype "passive"))
      (node (ref "Q17") (pin "1") (pinfunction "E_1") (pintype "passive"))
      (node (ref "Q2") (pin "1") (pinfunction "E_1") (pintype "passive"))
      (node (ref "Q3") (pin "1") (pinfunction "E_1") (pintype "passive"))
      (node (ref "Q4") (pin "1") (pinfunction "E_1") (pintype "passive"))
      (node (ref "Q5") (pin "1") (pinfunction "E_1") (pintype "passive"))
      (node (ref "Q6") (pin "1") (pinfunction "E_1") (pintype "passive"))
      (node (ref "Q7") (pin "1") (pinfunction "E_1") (pintype "passive"))
      (node (ref "Q8") (pin "1") (pinfunction "E_1") (pintype "passive"))
      (node (ref "Q9") (pin "1") (pinfunction "E_1") (pintype "passive"))
      (node (ref "R2") (pin "P$1") (pinfunction "1_P$1") (pintype "passive"))
      (node (ref "R21") (pin "P$1") (pinfunction "1_P$1") (pintype "passive"))
      (node (ref "R29") (pin "E") (pinfunction "E_E") (pintype "passive"))
      (node (ref "R31") (pin "P$1") (pinfunction "1_P$1") (pintype "passive"))
      (node (ref "U1") (pin "8") (pinfunction "P$V-_8") (pintype "bidirectional"))
      (node (ref "U2") (pin "8") (pinfunction "P$V-_8") (pintype "bidirectional"))
    )
    (net (code "83") (name "Net-(C1-+)") (class "Default")
      (node (ref "C1") (pin "1") (pinfunction "+_1") (pintype "passive"))
      (node (ref "IC1") (pin "1") (pinfunction "VI_1") (pintype "input"))
      (node (ref "J1") (pin "2") (pinfunction "2_2") (pintype "passive"))
    )
    (net (code "84") (name "Net-(R1-1)") (class "Default")
      (node (ref "D1") (pin "A") (pinfunction "A_A") (pintype "passive"))
      (node (ref "R1") (pin "P$1") (pinfunction "1_P$1") (pintype "passive"))
    )
    (net (code "85") (name "Net-(R3-1)") (class "Default")
      (node (ref "R3") (pin "P$1") (pinfunction "1_P$1") (pintype "passive"))
      (node (ref "U1") (pin "2") (pinfunction "Q1_2") (pintype "output"))
    )
    (net (code "86") (name "Net-(R4-1)") (class "Default")
      (node (ref "R4") (pin "P$1") (pinfunction "1_P$1") (pintype "passive"))
      (node (ref "U1") (pin "4") (pinfunction "Q2_4") (pintype "output"))
    )
    (net (code "87") (name "Net-(R5-1)") (class "Default")
      (node (ref "R5") (pin "P$1") (pinfunction "1_P$1") (pintype "passive"))
      (node (ref "U1") (pin "7") (pinfunction "Q3_7") (pintype "output"))
    )
    (net (code "88") (name "Net-(R6-1)") (class "Default")
      (node (ref "R6") (pin "P$1") (pinfunction "1_P$1") (pintype "passive"))
      (node (ref "U1") (pin "10") (pinfunction "Q4_10") (pintype "output"))
    )
    (net (code "89") (name "Net-(R7-1)") (class "Default")
      (node (ref "R7") (pin "P$1") (pinfunction "1_P$1") (pintype "passive"))
      (node (ref "U1") (pin "1") (pinfunction "Q5_1") (pintype "output"))
    )
    (net (code "90") (name "Net-(R8-1)") (class "Default")
      (node (ref "R8") (pin "P$1") (pinfunction "1_P$1") (pintype "passive"))
      (node (ref "U1") (pin "5") (pinfunction "Q6_5") (pintype "output"))
    )
    (net (code "91") (name "Net-(R9-1)") (class "Default")
      (node (ref "R9") (pin "P$1") (pinfunction "1_P$1") (pintype "passive"))
      (node (ref "U1") (pin "6") (pinfunction "Q7_6") (pintype "output"))
    )
    (net (code "92") (name "Net-(R10-1)") (class "Default")
      (node (ref "R10") (pin "P$1") (pinfunction "1_P$1") (pintype "passive"))
      (node (ref "U2") (pin "3") (pinfunction "Q0_3") (pintype "output"))
    )
    (net (code "93") (name "Net-(R11-1)") (class "Default")
      (node (ref "R11") (pin "P$1") (pinfunction "1_P$1") (pintype "passive"))
      (node (ref "U2") (pin "2") (pinfunction "Q1_2") (pintype "output"))
    )
    (net (code "94") (name "Net-(R12-1)") (class "Default")
      (node (ref "R12") (pin "P$1") (pinfunction "1_P$1") (pintype "passive"))
      (node (ref "U2") (pin "4") (pinfunction "Q2_4") (pintype "output"))
    )
    (net (code "95") (name "Net-(R13-1)") (class "Default")
      (node (ref "R13") (pin "P$1") (pinfunction "1_P$1") (pintype "passive"))
      (node (ref "U2") (pin "7") (pinfunction "Q3_7") (pintype "output"))
    )
    (net (code "96") (name "Net-(R14-1)") (class "Default")
      (node (ref "R14") (pin "P$1") (pinfunction "1_P$1") (pintype "passive"))
      (node (ref "U2") (pin "10") (pinfunction "Q4_10") (pintype "output"))
    )
    (net (code "97") (name "Net-(R15-1)") (class "Default")
      (node (ref "R15") (pin "P$1") (pinfunction "1_P$1") (pintype "passive"))
      (node (ref "U2") (pin "1") (pinfunction "Q5_1") (pintype "output"))
    )
    (net (code "98") (name "Net-(R16-1)") (class "Default")
      (node (ref "R16") (pin "P$1") (pinfunction "1_P$1") (pintype "passive"))
      (node (ref "U2") (pin "5") (pinfunction "Q6_5") (pintype "output"))
    )
    (net (code "99") (name "Net-(R17-1)") (class "Default")
      (node (ref "R17") (pin "P$1") (pinfunction "1_P$1") (pintype "passive"))
      (node (ref "U2") (pin "6") (pinfunction "Q7_6") (pintype "output"))
    )
    (net (code "100") (name "Net-(R18-1)") (class "Default")
      (node (ref "R18") (pin "P$1") (pinfunction "1_P$1") (pintype "passive"))
      (node (ref "U2") (pin "9") (pinfunction "Q8_9") (pintype "output"))
    )
    (net (code "101") (name "Net-(R21-2)") (class "Default")
      (node (ref "C4") (pin "2") (pinfunction "2_2") (pintype "passive"))
      (node (ref "R21") (pin "P$2") (pinfunction "2_P$2") (pintype "passive"))
      (node (ref "U2") (pin "15") (pinfunction "RES_15") (pintype "input"))
    )
    (net (code "102") (name "Net-(R28-1)") (class "Default")
      (node (ref "R28") (pin "P$1") (pinfunction "1_P$1") (pintype "passive"))
      (node (ref "R33") (pin "P$1") (pinfunction "1_P$1") (pintype "passive"))
      (node (ref "U1") (pin "3") (pinfunction "Q0_3") (pintype "output"))
    )
    (net (code "103") (name "Net-(R31-2)") (class "Default")
      (node (ref "C5") (pin "2") (pinfunction "2_2") (pintype "passive"))
      (node (ref "R31") (pin "P$2") (pinfunction "2_P$2") (pintype "passive"))
      (node (ref "U1") (pin "15") (pinfunction "RES_15") (pintype "input"))
    )
    (net (code "104") (name "Net-(U1A-ENA)") (class "Default")
      (node (ref "C4") (pin "1") (pinfunction "1_1") (pintype "passive"))
      (node (ref "U1") (pin "13") (pinfunction "ENA_13") (pintype "input"))
      (node (ref "U1") (pin "9") (pinfunction "Q8_9") (pintype "output"))
    )
    (net (code "105") (name "Net-(U2A-ENA)") (class "Default")
      (node (ref "C5") (pin "1") (pinfunction "1_1") (pintype "passive"))
      (node (ref "U2") (pin "11") (pinfunction "Q9_11") (pintype "output"))
      (node (ref "U2") (pin "13") (pinfunction "ENA_13") (pintype "input"))
    )
    (net (code "106") (name "VCC") (class "Default")
      (node (ref "C2") (pin "1") (pinfunction "+_1") (pintype "passive"))
      (node (ref "C3") (pin "1") (pinfunction "1_1") (pintype "passive"))
      (node (ref "C7") (pin "1") (pinfunction "+_1") (pintype "passive"))
      (node (ref "IC1") (pin "3") (pinfunction "VO_3") (pintype "passive"))
      (node (ref "IC2") (pin "40") (pinfunction "VCC_40") (pintype "power_in"))
      (node (ref "J20") (pin "1") (pinfunction "1_1") (pintype "passive"))
      (node (ref "J21") (pin "1") (pinfunction "1_1") (pintype "passive"))
      (node (ref "J22") (pin "1") (pinfunction "1_1") (pintype "passive"))
      (node (ref "J23") (pin "1") (pinfunction "1_1") (pintype "passive"))
      (node (ref "J24") (pin "1") (pinfunction "1_1") (pintype "passive"))
      (node (ref "J25") (pin "1") (pinfunction "1_1") (pintype "passive"))
      (node (ref "J26") (pin "1") (pinfunction "1_1") (pintype "passive"))
      (node (ref "J27") (pin "1") (pinfunction "1_1") (pintype "passive"))
      (node (ref "J5") (pin "20") (pinfunction "20_20") (pintype "passive"))
      (node (ref "J8") (pin "2") (pinfunction "2_2") (pintype "passive"))
      (node (ref "R1") (pin "P$2") (pinfunction "2_P$2") (pintype "passive"))
      (node (ref "R29") (pin "A") (pinfunction "A_A") (pintype "passive"))
      (node (ref "R30") (pin "P$1") (pinfunction "1_P$1") (pintype "passive"))
      (node (ref "U1") (pin "16") (pinfunction "P$V+_16") (pintype "bidirectional"))
      (node (ref "U2") (pin "16") (pinfunction "P$V+_16") (pintype "bidirectional"))
    )
    (net (code "107") (name "unconnected-(U1A-CO-Pad12)") (class "Default")
      (node (ref "U1") (pin "12") (pinfunction "CO_12") (pintype "output"))
    )
    (net (code "108") (name "unconnected-(U1A-Q9-Pad11)") (class "Default")
      (node (ref "U1") (pin "11") (pinfunction "Q9_11") (pintype "output"))
    )
    (net (code "109") (name "unconnected-(U2A-CO-Pad12)") (class "Default")
      (node (ref "U2") (pin "12") (pinfunction "CO_12") (pintype "output"))
    )
  )
)
